# Console.net
KiCad netlist of a schematic drawn in EAGLE
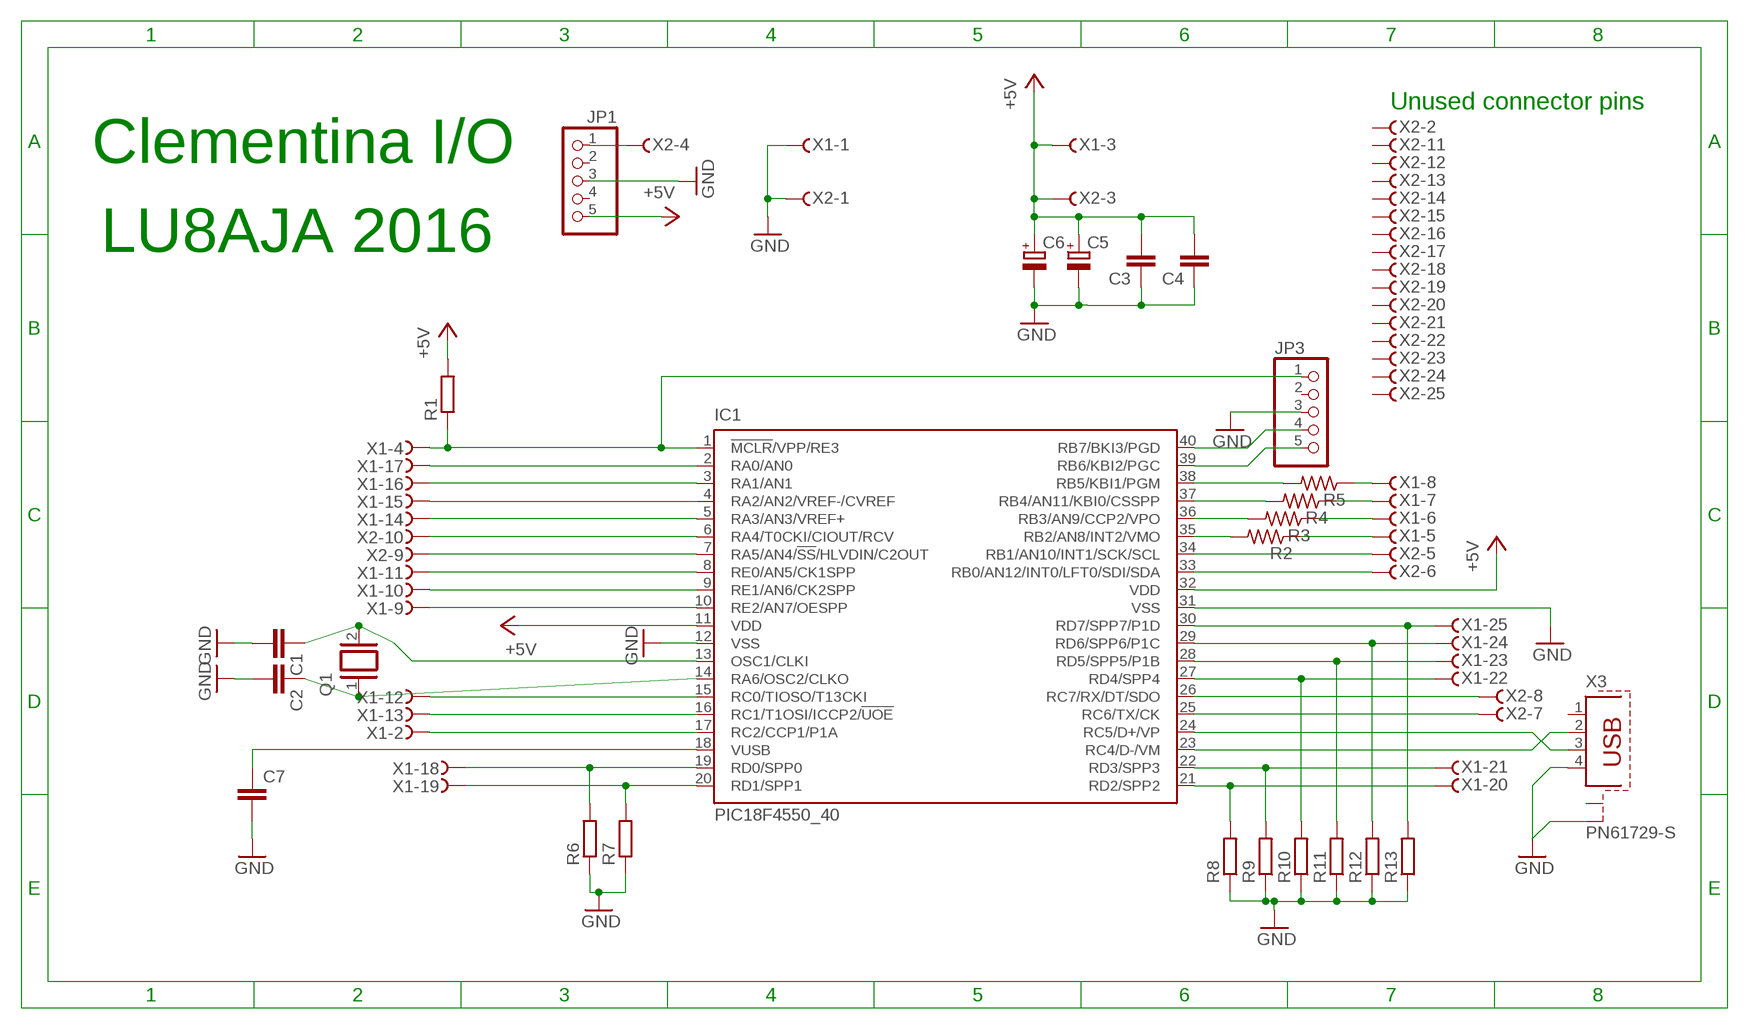
[diagram p0: schematic, sheet 1]

(export (version "E")
  (design (tool "Eeschema 10.0.6"))
  (components
    (comp (ref "C1")
      (value "C-EU025-025X050")
      (footprint "eagle-import:C025-025X050")
      (libsource (lib "eagle-import") (part "C-EU025-025X050"))
    )
    (comp (ref "C2")
      (value "C-EU025-025X050")
      (footprint "eagle-import:C025-025X050")
      (libsource (lib "eagle-import") (part "C-EU025-025X050"))
    )
    (comp (ref "C3")
      (value "C-EU050-025X075")
      (footprint "eagle-import:C050-025X075")
      (libsource (lib "eagle-import") (part "C-EU050-025X075"))
    )
    (comp (ref "C4")
      (value "C-EU050-030X075")
      (footprint "eagle-import:C050-030X075")
      (libsource (lib "eagle-import") (part "resistor_C-EU050-030X075"))
    )
    (comp (ref "C5")
      (value "CPOL-EUE5-8.5")
      (footprint "eagle-import:E5-8,5")
      (libsource (lib "eagle-import") (part "CPOL-EUE5-8.5"))
    )
    (comp (ref "C6")
      (value "CPOL-EUE5-8.5")
      (footprint "eagle-import:E5-8,5")
      (libsource (lib "eagle-import") (part "CPOL-EUE5-8.5"))
    )
    (comp (ref "C7")
      (value "C-EU050-025X075")
      (footprint "eagle-import:C050-025X075")
      (libsource (lib "eagle-import") (part "C-EU050-025X075"))
    )
    (comp (ref "IC1")
      (value "PIC18F4550_40")
      (footprint "eagle-import:DIL40")
      (fields (field (name "MF") "MICROCHIP") (field (name "MPN") "PIC18F4550-I/P"))
      (libsource (lib "eagle-import") (part "PIC18F4_40550"))
    )
    (comp (ref "JP1")
      (value "PINHD-1X5")
      (footprint "eagle-import:1X05")
      (libsource (lib "eagle-import") (part "PINHD-1X5"))
    )
    (comp (ref "JP3")
      (value "PINHD-1X5")
      (footprint "eagle-import:1X05")
      (libsource (lib "eagle-import") (part "PINHD-1X5"))
    )
    (comp (ref "Q1")
      (value "XTAL/S")
      (footprint "eagle-import:QS")
      (libsource (lib "eagle-import") (part "XTAL/S"))
    )
    (comp (ref "R1")
      (value "R-EU_0207/15")
      (footprint "eagle-import:0207_15")
      (libsource (lib "eagle-import") (part "R-EU_0207/15"))
    )
    (comp (ref "R2")
      (value "R-US_0207/15")
      (footprint "eagle-import:0207_15")
      (libsource (lib "eagle-import") (part "R-US_0207/15"))
    )
    (comp (ref "R3")
      (value "R-US_0207/15")
      (footprint "eagle-import:0207_15")
      (libsource (lib "eagle-import") (part "R-US_0207/15"))
    )
    (comp (ref "R4")
      (value "R-US_0207/15")
      (footprint "eagle-import:0207_15")
      (libsource (lib "eagle-import") (part "R-US_0207/15"))
    )
    (comp (ref "R5")
      (value "R-US_0207/15")
      (footprint "eagle-import:0207_15")
      (libsource (lib "eagle-import") (part "R-US_0207/15"))
    )
    (comp (ref "R6")
      (value "R-EU_0207/15")
      (footprint "eagle-import:0207_15")
      (libsource (lib "eagle-import") (part "R-EU_0207/15"))
    )
    (comp (ref "R7")
      (value "R-EU_0207/15")
      (footprint "eagle-import:0207_15")
      (libsource (lib "eagle-import") (part "R-EU_0207/15"))
    )
    (comp (ref "R8")
      (value "R-EU_0207/15")
      (footprint "eagle-import:0207_15")
      (libsource (lib "eagle-import") (part "R-EU_0207/15"))
    )
    (comp (ref "R9")
      (value "R-EU_0207/15")
      (footprint "eagle-import:0207_15")
      (libsource (lib "eagle-import") (part "R-EU_0207/15"))
    )
    (comp (ref "R10")
      (value "R-EU_0207/15")
      (footprint "eagle-import:0207_15")
      (libsource (lib "eagle-import") (part "R-EU_0207/15"))
    )
    (comp (ref "R11")
      (value "R-EU_0207/15")
      (footprint "eagle-import:0207_15")
      (libsource (lib "eagle-import") (part "R-EU_0207/15"))
    )
    (comp (ref "R12")
      (value "R-EU_0207/15")
      (footprint "eagle-import:0207_15")
      (libsource (lib "eagle-import") (part "R-EU_0207/15"))
    )
    (comp (ref "R13")
      (value "R-EU_0207/15")
      (footprint "eagle-import:0207_15")
      (libsource (lib "eagle-import") (part "R-EU_0207/15"))
    )
    (comp (ref "X1")
      (value "F25HPS")
      (footprint "eagle-import:F25HP")
      (libsource (lib "eagle-import") (part "F25HPS"))
    )
    (comp (ref "X2")
      (value "F25HPS")
      (footprint "eagle-import:F25HP")
      (libsource (lib "eagle-import") (part "F25HPS"))
    )
    (comp (ref "X3")
      (value "PN61729-S")
      (footprint "eagle-import:PN61729-S")
      (libsource (lib "eagle-import") (part "PN61729-S"))
    )
  )
  (nets
    (net (code "1") (name "+5V") (class "Default")
      (node (ref "C3") (pin "2") (pinfunction "2_2") (pintype "passive"))
      (node (ref "C4") (pin "2") (pinfunction "2_2") (pintype "passive"))
      (node (ref "C5") (pin "+") (pinfunction "+_+") (pintype "passive"))
      (node (ref "C6") (pin "+") (pinfunction "+_+") (pintype "passive"))
      (node (ref "IC1") (pin "11") (pinfunction "VDD_11") (pintype "power_in"))
      (node (ref "IC1") (pin "32") (pinfunction "VDD_32") (pintype "power_in"))
      (node (ref "JP1") (pin "5") (pinfunction "5_5") (pintype "passive"))
      (node (ref "R1") (pin "2") (pinfunction "2_2") (pintype "passive"))
      (node (ref "X1") (pin "3") (pinfunction "F_3") (pintype "passive"))
      (node (ref "X2") (pin "3") (pinfunction "F_3") (pintype "passive"))
    )
    (net (code "2") (name "GND") (class "Default")
      (node (ref "C1") (pin "2") (pinfunction "2_2") (pintype "passive"))
      (node (ref "C2") (pin "2") (pinfunction "2_2") (pintype "passive"))
      (node (ref "C3") (pin "1") (pinfunction "1_1") (pintype "passive"))
      (node (ref "C4") (pin "1") (pinfunction "1_1") (pintype "passive"))
      (node (ref "C5") (pin "-") (pinfunction "-_-") (pintype "passive"))
      (node (ref "C6") (pin "-") (pinfunction "-_-") (pintype "passive"))
      (node (ref "C7") (pin "2") (pinfunction "2_2") (pintype "passive"))
      (node (ref "IC1") (pin "12") (pinfunction "VSS_12") (pintype "power_in"))
      (node (ref "IC1") (pin "31") (pinfunction "VSS_31") (pintype "power_in"))
      (node (ref "JP1") (pin "3") (pinfunction "3_3") (pintype "passive"))
      (node (ref "JP3") (pin "3") (pinfunction "3_3") (pintype "passive"))
      (node (ref "R10") (pin "1") (pinfunction "1_1") (pintype "passive"))
      (node (ref "R11") (pin "1") (pinfunction "1_1") (pintype "passive"))
      (node (ref "R12") (pin "1") (pinfunction "1_1") (pintype "passive"))
      (node (ref "R13") (pin "1") (pinfunction "1_1") (pintype "passive"))
      (node (ref "R6") (pin "1") (pinfunction "1_1") (pintype "passive"))
      (node (ref "R7") (pin "1") (pinfunction "1_1") (pintype "passive"))
      (node (ref "R8") (pin "1") (pinfunction "1_1") (pintype "passive"))
      (node (ref "R9") (pin "1") (pinfunction "1_1") (pintype "passive"))
      (node (ref "X1") (pin "1") (pinfunction "F_1") (pintype "passive"))
      (node (ref "X2") (pin "1") (pinfunction "F_1") (pintype "passive"))
      (node (ref "X3") (pin "4") (pinfunction "4_4") (pintype "passive"))
      (node (ref "X3") (pin "S2") (pinfunction "S2_S2") (pintype "passive"))
    )
    (net (code "3") (name "Net-(IC1-OSC1{slash}CLKI)") (class "Default")
      (node (ref "C1") (pin "1") (pinfunction "1_1") (pintype "passive"))
      (node (ref "IC1") (pin "13") (pinfunction "OSC1/CLKI_13") (pintype "input"))
      (node (ref "Q1") (pin "2") (pinfunction "2_2") (pintype "passive"))
    )
    (net (code "4") (name "Net-(IC1-RA0{slash}AN0)") (class "Default")
      (node (ref "IC1") (pin "2") (pinfunction "RA0/AN0_2") (pintype "bidirectional"))
      (node (ref "X1") (pin "17") (pinfunction "F_17") (pintype "passive"))
    )
    (net (code "5") (name "Net-(IC1-RA1{slash}AN1)") (class "Default")
      (node (ref "IC1") (pin "3") (pinfunction "RA1/AN1_3") (pintype "bidirectional"))
      (node (ref "X1") (pin "16") (pinfunction "F_16") (pintype "passive"))
    )
    (net (code "6") (name "Net-(IC1-RA2{slash}AN2{slash}VREF-{slash}CVREF)") (class "Default")
      (node (ref "IC1") (pin "4") (pinfunction "RA2/AN2/VREF-/CVREF_4") (pintype "bidirectional"))
      (node (ref "X1") (pin "15") (pinfunction "F_15") (pintype "passive"))
    )
    (net (code "7") (name "Net-(IC1-RA3{slash}AN3{slash}VREF+)") (class "Default")
      (node (ref "IC1") (pin "5") (pinfunction "RA3/AN3/VREF+_5") (pintype "bidirectional"))
      (node (ref "X1") (pin "14") (pinfunction "F_14") (pintype "passive"))
    )
    (net (code "8") (name "Net-(IC1-RA4{slash}T0CKI{slash}CIOUT{slash}RCV)") (class "Default")
      (node (ref "IC1") (pin "6") (pinfunction "RA4/T0CKI/CIOUT/RCV_6") (pintype "bidirectional"))
      (node (ref "X2") (pin "10") (pinfunction "F_10") (pintype "passive"))
    )
    (net (code "9") (name "Net-(IC1-RA5{slash}AN4{slash}~{SS}{slash}HLVDIN{slash}C2OUT)") (class "Default")
      (node (ref "IC1") (pin "7") (pinfunction "RA5/AN4/~{SS}/HLVDIN/C2OUT_7") (pintype "bidirectional"))
      (node (ref "X2") (pin "9") (pinfunction "F_9") (pintype "passive"))
    )
    (net (code "10") (name "Net-(IC1-RA6{slash}OSC2{slash}CLKO)") (class "Default")
      (node (ref "C2") (pin "1") (pinfunction "1_1") (pintype "passive"))
      (node (ref "IC1") (pin "14") (pinfunction "RA6/OSC2/CLKO_14") (pintype "output"))
      (node (ref "Q1") (pin "1") (pinfunction "1_1") (pintype "passive"))
    )
    (net (code "11") (name "Net-(IC1-RB0{slash}AN12{slash}INT0{slash}LFT0{slash}SDI{slash}SDA)") (class "Default")
      (node (ref "IC1") (pin "33") (pinfunction "RB0/AN12/INT0/LFT0/SDI/SDA_33") (pintype "bidirectional"))
      (node (ref "X2") (pin "6") (pinfunction "F_6") (pintype "passive"))
    )
    (net (code "12") (name "Net-(IC1-RB1{slash}AN10{slash}INT1{slash}SCK{slash}SCL)") (class "Default")
      (node (ref "IC1") (pin "34") (pinfunction "RB1/AN10/INT1/SCK/SCL_34") (pintype "bidirectional"))
      (node (ref "X2") (pin "5") (pinfunction "F_5") (pintype "passive"))
    )
    (net (code "13") (name "Net-(IC1-RB2{slash}AN8{slash}INT2{slash}VMO)") (class "Default")
      (node (ref "IC1") (pin "35") (pinfunction "RB2/AN8/INT2/VMO_35") (pintype "bidirectional"))
      (node (ref "R2") (pin "2") (pinfunction "2_2") (pintype "passive"))
    )
    (net (code "14") (name "Net-(IC1-RB3{slash}AN9{slash}CCP2{slash}VPO)") (class "Default")
      (node (ref "IC1") (pin "36") (pinfunction "RB3/AN9/CCP2/VPO_36") (pintype "bidirectional"))
      (node (ref "R3") (pin "2") (pinfunction "2_2") (pintype "passive"))
    )
    (net (code "15") (name "Net-(IC1-RB4{slash}AN11{slash}KBI0{slash}CSSPP)") (class "Default")
      (node (ref "IC1") (pin "37") (pinfunction "RB4/AN11/KBI0/CSSPP_37") (pintype "bidirectional"))
      (node (ref "R4") (pin "2") (pinfunction "2_2") (pintype "passive"))
    )
    (net (code "16") (name "Net-(IC1-RB5{slash}KBI1{slash}PGM)") (class "Default")
      (node (ref "IC1") (pin "38") (pinfunction "RB5/KBI1/PGM_38") (pintype "bidirectional"))
      (node (ref "R5") (pin "2") (pinfunction "2_2") (pintype "passive"))
    )
    (net (code "17") (name "Net-(IC1-RB6{slash}KBI2{slash}PGC)") (class "Default")
      (node (ref "IC1") (pin "39") (pinfunction "RB6/KBI2/PGC_39") (pintype "bidirectional"))
      (node (ref "JP3") (pin "5") (pinfunction "5_5") (pintype "passive"))
    )
    (net (code "18") (name "Net-(IC1-RB7{slash}BKI3{slash}PGD)") (class "Default")
      (node (ref "IC1") (pin "40") (pinfunction "RB7/BKI3/PGD_40") (pintype "bidirectional"))
      (node (ref "JP3") (pin "4") (pinfunction "4_4") (pintype "passive"))
    )
    (net (code "19") (name "Net-(IC1-RC0{slash}TIOSO{slash}T13CKI)") (class "Default")
      (node (ref "IC1") (pin "15") (pinfunction "RC0/TIOSO/T13CKI_15") (pintype "bidirectional"))
      (node (ref "X1") (pin "12") (pinfunction "F_12") (pintype "passive"))
    )
    (net (code "20") (name "Net-(IC1-RC1{slash}T1OSI{slash}ICCP2{slash}~{UOE})") (class "Default")
      (node (ref "IC1") (pin "16") (pinfunction "RC1/T1OSI/ICCP2/~{UOE}_16") (pintype "bidirectional"))
      (node (ref "X1") (pin "13") (pinfunction "F_13") (pintype "passive"))
    )
    (net (code "21") (name "Net-(IC1-RC2{slash}CCP1{slash}P1A)") (class "Default")
      (node (ref "IC1") (pin "17") (pinfunction "RC2/CCP1/P1A_17") (pintype "bidirectional"))
      (node (ref "X1") (pin "2") (pinfunction "F_2") (pintype "passive"))
    )
    (net (code "22") (name "Net-(IC1-RC4{slash}D-{slash}VM)") (class "Default")
      (node (ref "IC1") (pin "23") (pinfunction "RC4/D-/VM_23") (pintype "bidirectional"))
      (node (ref "X3") (pin "2") (pinfunction "2_2") (pintype "passive"))
    )
    (net (code "23") (name "Net-(IC1-RC5{slash}D+{slash}VP)") (class "Default")
      (node (ref "IC1") (pin "24") (pinfunction "RC5/D+/VP_24") (pintype "bidirectional"))
      (node (ref "X3") (pin "3") (pinfunction "3_3") (pintype "passive"))
    )
    (net (code "24") (name "Net-(IC1-RC6{slash}TX{slash}CK)") (class "Default")
      (node (ref "IC1") (pin "25") (pinfunction "RC6/TX/CK_25") (pintype "bidirectional"))
      (node (ref "X2") (pin "7") (pinfunction "F_7") (pintype "passive"))
    )
    (net (code "25") (name "Net-(IC1-RC7{slash}RX{slash}DT{slash}SDO)") (class "Default")
      (node (ref "IC1") (pin "26") (pinfunction "RC7/RX/DT/SDO_26") (pintype "bidirectional"))
      (node (ref "X2") (pin "8") (pinfunction "F_8") (pintype "passive"))
    )
    (net (code "26") (name "Net-(IC1-RD0{slash}SPP0)") (class "Default")
      (node (ref "IC1") (pin "19") (pinfunction "RD0/SPP0_19") (pintype "bidirectional"))
      (node (ref "R6") (pin "2") (pinfunction "2_2") (pintype "passive"))
      (node (ref "X1") (pin "18") (pinfunction "F_18") (pintype "passive"))
    )
    (net (code "27") (name "Net-(IC1-RD1{slash}SPP1)") (class "Default")
      (node (ref "IC1") (pin "20") (pinfunction "RD1/SPP1_20") (pintype "bidirectional"))
      (node (ref "R7") (pin "2") (pinfunction "2_2") (pintype "passive"))
      (node (ref "X1") (pin "19") (pinfunction "F_19") (pintype "passive"))
    )
    (net (code "28") (name "Net-(IC1-RD2{slash}SPP2)") (class "Default")
      (node (ref "IC1") (pin "21") (pinfunction "RD2/SPP2_21") (pintype "bidirectional"))
      (node (ref "R8") (pin "2") (pinfunction "2_2") (pintype "passive"))
      (node (ref "X1") (pin "20") (pinfunction "F_20") (pintype "passive"))
    )
    (net (code "29") (name "Net-(IC1-RD3{slash}SPP3)") (class "Default")
      (node (ref "IC1") (pin "22") (pinfunction "RD3/SPP3_22") (pintype "bidirectional"))
      (node (ref "R9") (pin "2") (pinfunction "2_2") (pintype "passive"))
      (node (ref "X1") (pin "21") (pinfunction "F_21") (pintype "passive"))
    )
    (net (code "30") (name "Net-(IC1-RD4{slash}SPP4)") (class "Default")
      (node (ref "IC1") (pin "27") (pinfunction "RD4/SPP4_27") (pintype "bidirectional"))
      (node (ref "R10") (pin "2") (pinfunction "2_2") (pintype "passive"))
      (node (ref "X1") (pin "22") (pinfunction "F_22") (pintype "passive"))
    )
    (net (code "31") (name "Net-(IC1-RD5{slash}SPP5{slash}P1B)") (class "Default")
      (node (ref "IC1") (pin "28") (pinfunction "RD5/SPP5/P1B_28") (pintype "bidirectional"))
      (node (ref "R11") (pin "2") (pinfunction "2_2") (pintype "passive"))
      (node (ref "X1") (pin "23") (pinfunction "F_23") (pintype "passive"))
    )
    (net (code "32") (name "Net-(IC1-RD6{slash}SPP6{slash}P1C)") (class "Default")
      (node (ref "IC1") (pin "29") (pinfunction "RD6/SPP6/P1C_29") (pintype "bidirectional"))
      (node (ref "R12") (pin "2") (pinfunction "2_2") (pintype "passive"))
      (node (ref "X1") (pin "24") (pinfunction "F_24") (pintype "passive"))
    )
    (net (code "33") (name "Net-(IC1-RD7{slash}SPP7{slash}P1D)") (class "Default")
      (node (ref "IC1") (pin "30") (pinfunction "RD7/SPP7/P1D_30") (pintype "bidirectional"))
      (node (ref "R13") (pin "2") (pinfunction "2_2") (pintype "passive"))
      (node (ref "X1") (pin "25") (pinfunction "F_25") (pintype "passive"))
    )
    (net (code "34") (name "Net-(IC1-RE0{slash}AN5{slash}CK1SPP)") (class "Default")
      (node (ref "IC1") (pin "8") (pinfunction "RE0/AN5/CK1SPP_8") (pintype "bidirectional"))
      (node (ref "X1") (pin "11") (pinfunction "F_11") (pintype "passive"))
    )
    (net (code "35") (name "Net-(IC1-RE1{slash}AN6{slash}CK2SPP)") (class "Default")
      (node (ref "IC1") (pin "9") (pinfunction "RE1/AN6/CK2SPP_9") (pintype "bidirectional"))
      (node (ref "X1") (pin "10") (pinfunction "F_10") (pintype "passive"))
    )
    (net (code "36") (name "Net-(IC1-RE2{slash}AN7{slash}OESPP)") (class "Default")
      (node (ref "IC1") (pin "10") (pinfunction "RE2/AN7/OESPP_10") (pintype "bidirectional"))
      (node (ref "X1") (pin "9") (pinfunction "F_9") (pintype "passive"))
    )
    (net (code "37") (name "Net-(IC1-VUSB)") (class "Default")
      (node (ref "C7") (pin "1") (pinfunction "1_1") (pintype "passive"))
      (node (ref "IC1") (pin "18") (pinfunction "VUSB_18") (pintype "bidirectional"))
    )
    (net (code "38") (name "Net-(IC1-~{MCLR}{slash}VPP{slash}RE3)") (class "Default")
      (node (ref "IC1") (pin "1") (pinfunction "~{MCLR}/VPP/RE3_1") (pintype "input"))
      (node (ref "JP3") (pin "1") (pinfunction "1_1") (pintype "passive"))
      (node (ref "R1") (pin "1") (pinfunction "1_1") (pintype "passive"))
      (node (ref "X1") (pin "4") (pinfunction "F_4") (pintype "passive"))
    )
    (net (code "39") (name "Net-(X1U-F)") (class "Default")
      (node (ref "R2") (pin "1") (pinfunction "1_1") (pintype "passive"))
      (node (ref "X1") (pin "5") (pinfunction "F_5") (pintype "passive"))
    )
    (net (code "40") (name "Net-(X1V-F)") (class "Default")
      (node (ref "R3") (pin "1") (pinfunction "1_1") (pintype "passive"))
      (node (ref "X1") (pin "6") (pinfunction "F_6") (pintype "passive"))
    )
    (net (code "41") (name "Net-(X1W-F)") (class "Default")
      (node (ref "R4") (pin "1") (pinfunction "1_1") (pintype "passive"))
      (node (ref "X1") (pin "7") (pinfunction "F_7") (pintype "passive"))
    )
    (net (code "42") (name "Net-(X1X-F)") (class "Default")
      (node (ref "R5") (pin "1") (pinfunction "1_1") (pintype "passive"))
      (node (ref "X1") (pin "8") (pinfunction "F_8") (pintype "passive"))
    )
    (net (code "43") (name "Net-(X2T-F)") (class "Default")
      (node (ref "JP1") (pin "1") (pinfunction "1_1") (pintype "passive"))
      (node (ref "X2") (pin "4") (pinfunction "F_4") (pintype "passive"))
    )
    (net (code "44") (name "unconnected-(JP1-Pad2)") (class "Default")
      (node (ref "JP1") (pin "2") (pinfunction "2_2") (pintype "passive"))
    )
    (net (code "45") (name "unconnected-(JP1-Pad4)") (class "Default")
      (node (ref "JP1") (pin "4") (pinfunction "4_4") (pintype "passive"))
    )
    (net (code "46") (name "unconnected-(JP3-Pad2)") (class "Default")
      (node (ref "JP3") (pin "2") (pinfunction "2_2") (pintype "passive"))
    )
    (net (code "47") (name "unconnected-(X2C-F-Pad11)") (class "Default")
      (node (ref "X2") (pin "11") (pinfunction "F_11") (pintype "passive"))
    )
    (net (code "48") (name "unconnected-(X2D-F-Pad12)") (class "Default")
      (node (ref "X2") (pin "12") (pinfunction "F_12") (pintype "passive"))
    )
    (net (code "49") (name "unconnected-(X2E-F-Pad13)") (class "Default")
      (node (ref "X2") (pin "13") (pinfunction "F_13") (pintype "passive"))
    )
    (net (code "50") (name "unconnected-(X2F-F-Pad14)") (class "Default")
      (node (ref "X2") (pin "14") (pinfunction "F_14") (pintype "passive"))
    )
    (net (code "51") (name "unconnected-(X2G-F-Pad15)") (class "Default")
      (node (ref "X2") (pin "15") (pinfunction "F_15") (pintype "passive"))
    )
    (net (code "52") (name "unconnected-(X2H-F-Pad16)") (class "Default")
      (node (ref "X2") (pin "16") (pinfunction "F_16") (pintype "passive"))
    )
    (net (code "53") (name "unconnected-(X2I-F-Pad17)") (class "Default")
      (node (ref "X2") (pin "17") (pinfunction "F_17") (pintype "passive"))
    )
    (net (code "54") (name "unconnected-(X2J-F-Pad18)") (class "Default")
      (node (ref "X2") (pin "18") (pinfunction "F_18") (pintype "passive"))
    )
    (net (code "55") (name "unconnected-(X2K-F-Pad19)") (class "Default")
      (node (ref "X2") (pin "19") (pinfunction "F_19") (pintype "passive"))
    )
    (net (code "56") (name "unconnected-(X2L-F-Pad2)") (class "Default")
      (node (ref "X2") (pin "2") (pinfunction "F_2") (pintype "passive"))
    )
    (net (code "57") (name "unconnected-(X2M-F-Pad20)") (class "Default")
      (node (ref "X2") (pin "20") (pinfunction "F_20") (pintype "passive"))
    )
    (net (code "58") (name "unconnected-(X2N-F-Pad21)") (class "Default")
      (node (ref "X2") (pin "21") (pinfunction "F_21") (pintype "passive"))
    )
    (net (code "59") (name "unconnected-(X2O-F-Pad22)") (class "Default")
      (node (ref "X2") (pin "22") (pinfunction "F_22") (pintype "passive"))
    )
    (net (code "60") (name "unconnected-(X2P-F-Pad23)") (class "Default")
      (node (ref "X2") (pin "23") (pinfunction "F_23") (pintype "passive"))
    )
    (net (code "61") (name "unconnected-(X2Q-F-Pad24)") (class "Default")
      (node (ref "X2") (pin "24") (pinfunction "F_24") (pintype "passive"))
    )
    (net (code "62") (name "unconnected-(X2R-F-Pad25)") (class "Default")
      (node (ref "X2") (pin "25") (pinfunction "F_25") (pintype "passive"))
    )
    (net (code "63") (name "unconnected-(X3-Pad1)") (class "Default")
      (node (ref "X3") (pin "1") (pinfunction "1_1") (pintype "passive"))
    )
    (net (code "64") (name "unconnected-(X3-PadS1)") (class "Default")
      (node (ref "X3") (pin "S1") (pinfunction "S1_S1") (pintype "passive"))
    )
  )
)
